# pc-001.net
KiCad netlist of a schematic drawn in EAGLE
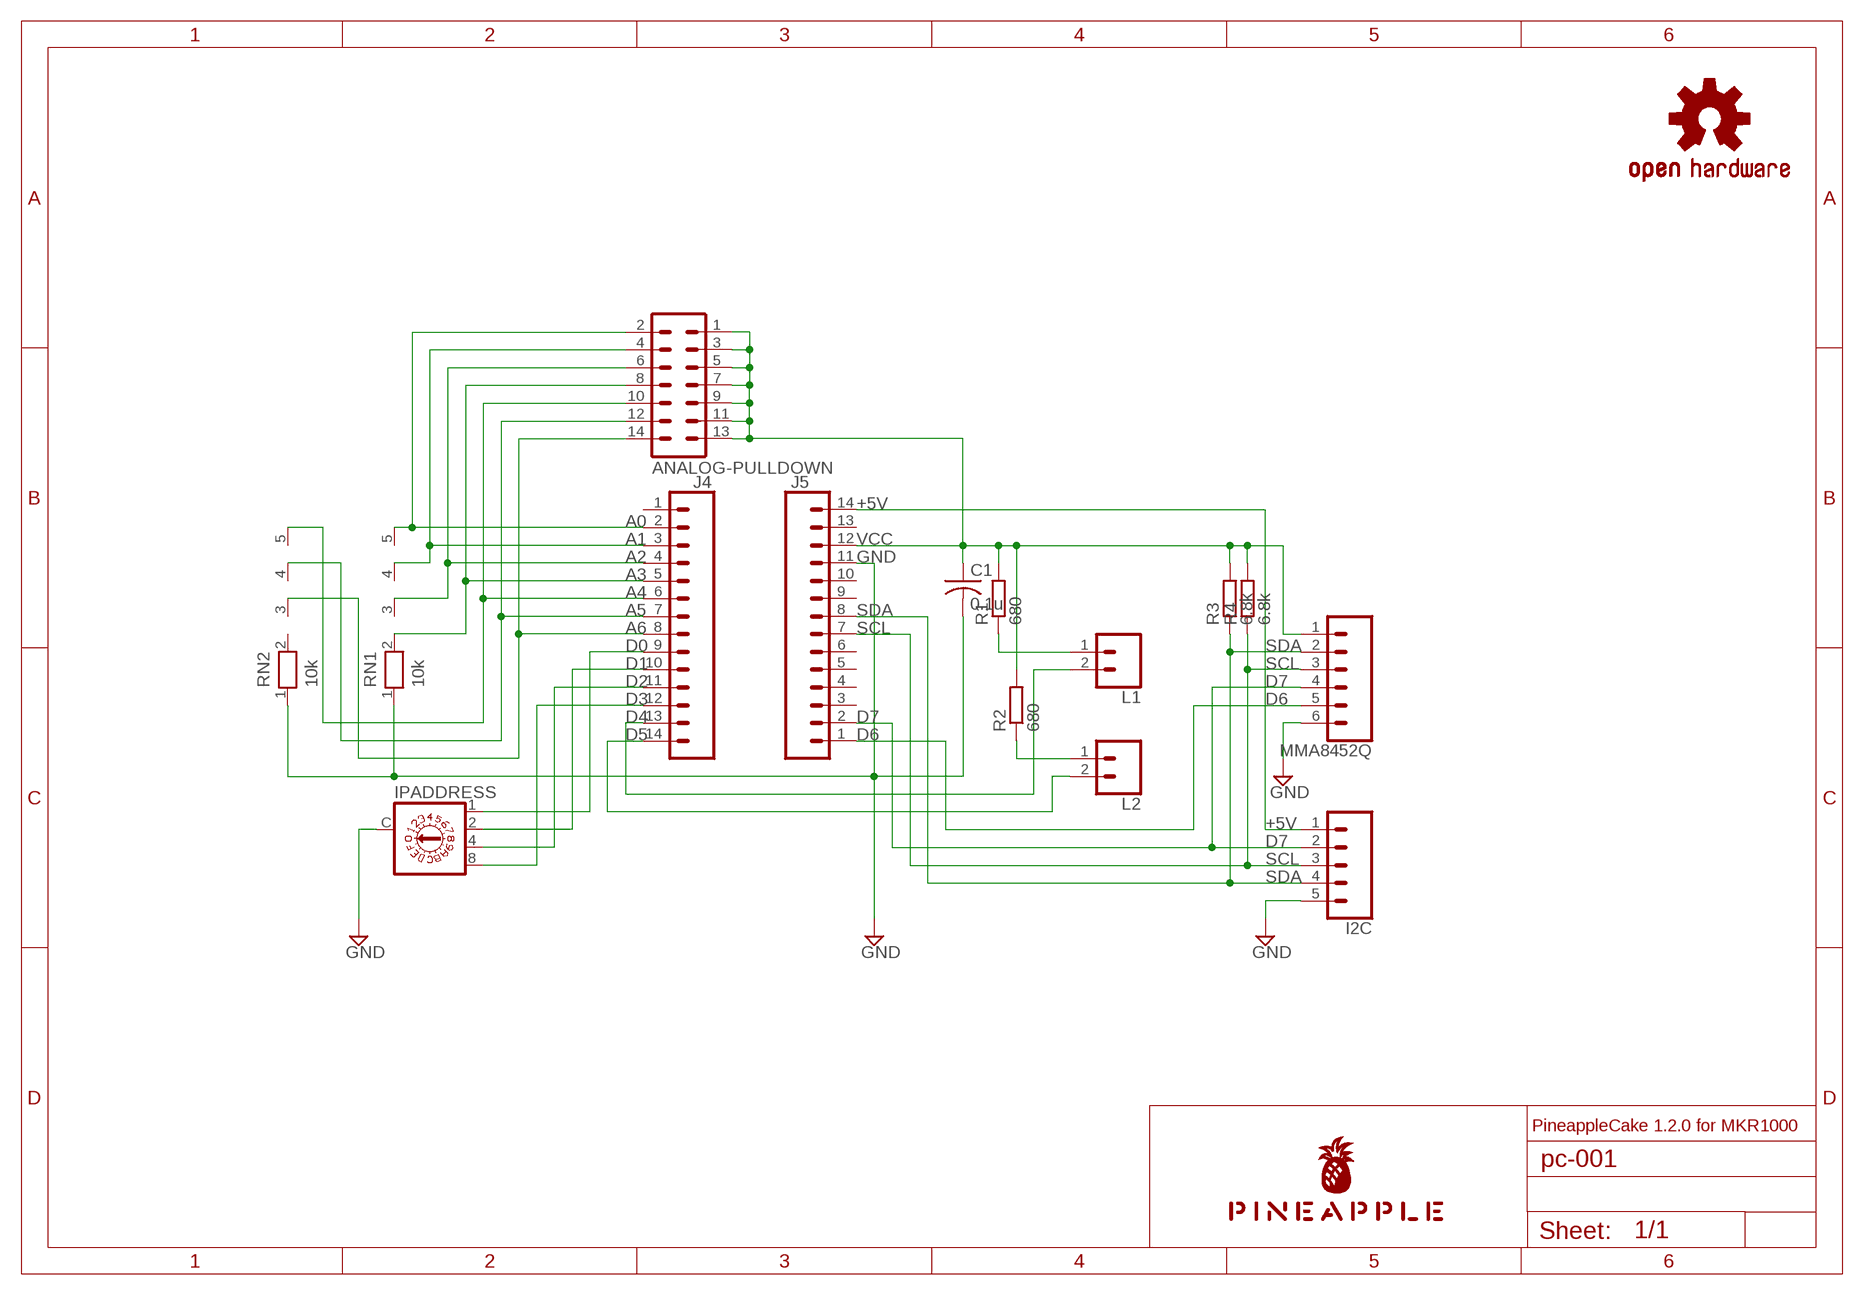
[diagram p0: schematic, sheet 1]

(export (version "E")
  (design (tool "Eeschema 10.0.6"))
  (components
    (comp (ref "ANALOG-PULLDOWN")
      (value "ML14L")
      (footprint "eagle-import:ML14L")
      (libsource (lib "eagle-import") (part "ML14L"))
    )
    (comp (ref "C1")
      (value "0.1u")
      (footprint "eagle-import:C025-025X050")
      (libsource (lib "eagle-import") (part "C-US025-025X050"))
    )
    (comp (ref "I2C")
      (value "CONN_05SMD")
      (footprint "eagle-import:1X05_1MM")
      (libsource (lib "eagle-import") (part "CONN_05SMD"))
    )
    (comp (ref "IPADDRESS")
      (value "A1353HEX")
      (footprint "eagle-import:A1353HEX")
      (libsource (lib "eagle-import") (part "A1353HEX"))
    )
    (comp (ref "J4")
      (value "DNP")
      (footprint "eagle-import:1X14")
      (libsource (lib "eagle-import") (part "CONN_14"))
    )
    (comp (ref "J5")
      (value "DNP")
      (footprint "eagle-import:1X14")
      (libsource (lib "eagle-import") (part "CONN_14"))
    )
    (comp (ref "L1")
      (value "CONN_02-JST-2-PTH-NO_SILK")
      (footprint "eagle-import:JST-2-PTH-NS")
      (libsource (lib "eagle-import") (part "CONN_02-JST-2-PTH-NO_SILK"))
    )
    (comp (ref "L2")
      (value "CONN_02-JST-2-PTH-NO_SILK")
      (footprint "eagle-import:JST-2-PTH-NS")
      (libsource (lib "eagle-import") (part "CONN_02-JST-2-PTH-NO_SILK"))
    )
    (comp (ref "LOGO1")
      (value "OSHW-LOGOS-COPPER")
      (footprint "eagle-import:OSHW-LOGO-S_COPPER")
      (libsource (lib "eagle-import") (part "OSHW-LOGOS-COPPER"))
    )
    (comp (ref "MMA8452Q")
      (value "CONN_06NO_SILK_FEMALE_PTH")
      (footprint "eagle-import:1X06_NO_SILK")
      (libsource (lib "eagle-import") (part "CONN_06NO_SILK_FEMALE_PTH"))
    )
    (comp (ref "R1")
      (value "680")
      (footprint "eagle-import:0204_5")
      (libsource (lib "eagle-import") (part "R-EU_0204/5"))
    )
    (comp (ref "R2")
      (value "680")
      (footprint "eagle-import:0204_5")
      (libsource (lib "eagle-import") (part "R-EU_0204/5"))
    )
    (comp (ref "R3")
      (value "6.8k")
      (footprint "eagle-import:0204_5")
      (libsource (lib "eagle-import") (part "R-EU_0204/5"))
    )
    (comp (ref "R4")
      (value "6.8k")
      (footprint "eagle-import:0204_5")
      (libsource (lib "eagle-import") (part "R-EU_0204/5"))
    )
    (comp (ref "RN1")
      (value "10k")
      (footprint "eagle-import:RN-5")
      (libsource (lib "eagle-import") (part "RN04"))
    )
    (comp (ref "RN2")
      (value "10k")
      (footprint "eagle-import:RN-5")
      (libsource (lib "eagle-import") (part "RN04"))
    )
    (comp (ref "U$1")
      (value "PINEAPPLE450")
      (footprint "eagle-import:PINEAPPLE450")
      (libsource (lib "eagle-import") (part "PINEAPPLE450"))
    )
  )
  (nets
    (net (code "1") (name "/+5V") (class "Default")
      (node (ref "I2C") (pin "1") (pinfunction "1_1") (pintype "passive"))
      (node (ref "J5") (pin "14") (pinfunction "14_14") (pintype "passive"))
    )
    (net (code "2") (name "/A0") (class "Default")
      (node (ref "ANALOG-PULLDOWN") (pin "2") (pinfunction "2_2") (pintype "passive"))
      (node (ref "J4") (pin "2") (pinfunction "2_2") (pintype "passive"))
      (node (ref "RN1") (pin "5") (pinfunction "5_5") (pintype "passive"))
    )
    (net (code "3") (name "/A1") (class "Default")
      (node (ref "ANALOG-PULLDOWN") (pin "4") (pinfunction "4_4") (pintype "passive"))
      (node (ref "J4") (pin "3") (pinfunction "3_3") (pintype "passive"))
      (node (ref "RN1") (pin "4") (pinfunction "4_4") (pintype "passive"))
    )
    (net (code "4") (name "/A2") (class "Default")
      (node (ref "ANALOG-PULLDOWN") (pin "6") (pinfunction "6_6") (pintype "passive"))
      (node (ref "J4") (pin "4") (pinfunction "4_4") (pintype "passive"))
      (node (ref "RN1") (pin "3") (pinfunction "3_3") (pintype "passive"))
    )
    (net (code "5") (name "/A3") (class "Default")
      (node (ref "ANALOG-PULLDOWN") (pin "8") (pinfunction "8_8") (pintype "passive"))
      (node (ref "J4") (pin "5") (pinfunction "5_5") (pintype "passive"))
      (node (ref "RN1") (pin "2") (pinfunction "2_2") (pintype "passive"))
    )
    (net (code "6") (name "/A4") (class "Default")
      (node (ref "ANALOG-PULLDOWN") (pin "10") (pinfunction "10_10") (pintype "passive"))
      (node (ref "J4") (pin "6") (pinfunction "6_6") (pintype "passive"))
      (node (ref "RN2") (pin "5") (pinfunction "5_5") (pintype "passive"))
    )
    (net (code "7") (name "/A5") (class "Default")
      (node (ref "ANALOG-PULLDOWN") (pin "12") (pinfunction "12_12") (pintype "passive"))
      (node (ref "J4") (pin "7") (pinfunction "7_7") (pintype "passive"))
      (node (ref "RN2") (pin "4") (pinfunction "4_4") (pintype "passive"))
    )
    (net (code "8") (name "/A6") (class "Default")
      (node (ref "ANALOG-PULLDOWN") (pin "14") (pinfunction "14_14") (pintype "passive"))
      (node (ref "J4") (pin "8") (pinfunction "8_8") (pintype "passive"))
      (node (ref "RN2") (pin "3") (pinfunction "3_3") (pintype "passive"))
    )
    (net (code "9") (name "/D0") (class "Default")
      (node (ref "IPADDRESS") (pin "1") (pinfunction "1_1") (pintype "passive"))
      (node (ref "J4") (pin "9") (pinfunction "9_9") (pintype "passive"))
    )
    (net (code "10") (name "/D1") (class "Default")
      (node (ref "IPADDRESS") (pin "2") (pinfunction "2_2") (pintype "passive"))
      (node (ref "J4") (pin "10") (pinfunction "10_10") (pintype "passive"))
    )
    (net (code "11") (name "/D2") (class "Default")
      (node (ref "IPADDRESS") (pin "4") (pinfunction "4_4") (pintype "passive"))
      (node (ref "J4") (pin "11") (pinfunction "11_11") (pintype "passive"))
    )
    (net (code "12") (name "/D3") (class "Default")
      (node (ref "IPADDRESS") (pin "8") (pinfunction "8_8") (pintype "passive"))
      (node (ref "J4") (pin "12") (pinfunction "12_12") (pintype "passive"))
    )
    (net (code "13") (name "/D4") (class "Default")
      (node (ref "J4") (pin "13") (pinfunction "13_13") (pintype "passive"))
      (node (ref "L1") (pin "2") (pinfunction "2_2") (pintype "passive"))
    )
    (net (code "14") (name "/D5") (class "Default")
      (node (ref "J4") (pin "14") (pinfunction "14_14") (pintype "passive"))
      (node (ref "L2") (pin "2") (pinfunction "2_2") (pintype "passive"))
    )
    (net (code "15") (name "/D6") (class "Default")
      (node (ref "J5") (pin "1") (pinfunction "1_1") (pintype "passive"))
      (node (ref "MMA8452Q") (pin "5") (pinfunction "5_5") (pintype "passive"))
    )
    (net (code "16") (name "/D7") (class "Default")
      (node (ref "I2C") (pin "2") (pinfunction "2_2") (pintype "passive"))
      (node (ref "J5") (pin "2") (pinfunction "2_2") (pintype "passive"))
      (node (ref "MMA8452Q") (pin "4") (pinfunction "4_4") (pintype "passive"))
    )
    (net (code "17") (name "/SCL") (class "Default")
      (node (ref "I2C") (pin "3") (pinfunction "3_3") (pintype "passive"))
      (node (ref "J5") (pin "7") (pinfunction "7_7") (pintype "passive"))
      (node (ref "MMA8452Q") (pin "3") (pinfunction "3_3") (pintype "passive"))
      (node (ref "R4") (pin "1") (pinfunction "1_1") (pintype "passive"))
    )
    (net (code "18") (name "/SDA") (class "Default")
      (node (ref "I2C") (pin "4") (pinfunction "4_4") (pintype "passive"))
      (node (ref "J5") (pin "8") (pinfunction "8_8") (pintype "passive"))
      (node (ref "MMA8452Q") (pin "2") (pinfunction "2_2") (pintype "passive"))
      (node (ref "R3") (pin "1") (pinfunction "1_1") (pintype "passive"))
    )
    (net (code "19") (name "/VCC") (class "Default")
      (node (ref "ANALOG-PULLDOWN") (pin "1") (pinfunction "1_1") (pintype "passive"))
      (node (ref "ANALOG-PULLDOWN") (pin "11") (pinfunction "11_11") (pintype "passive"))
      (node (ref "ANALOG-PULLDOWN") (pin "13") (pinfunction "13_13") (pintype "passive"))
      (node (ref "ANALOG-PULLDOWN") (pin "3") (pinfunction "3_3") (pintype "passive"))
      (node (ref "ANALOG-PULLDOWN") (pin "5") (pinfunction "5_5") (pintype "passive"))
      (node (ref "ANALOG-PULLDOWN") (pin "7") (pinfunction "7_7") (pintype "passive"))
      (node (ref "ANALOG-PULLDOWN") (pin "9") (pinfunction "9_9") (pintype "passive"))
      (node (ref "C1") (pin "1") (pinfunction "1_1") (pintype "passive"))
      (node (ref "J5") (pin "12") (pinfunction "12_12") (pintype "passive"))
      (node (ref "MMA8452Q") (pin "1") (pinfunction "1_1") (pintype "passive"))
      (node (ref "R1") (pin "2") (pinfunction "2_2") (pintype "passive"))
      (node (ref "R2") (pin "2") (pinfunction "2_2") (pintype "passive"))
      (node (ref "R3") (pin "2") (pinfunction "2_2") (pintype "passive"))
      (node (ref "R4") (pin "2") (pinfunction "2_2") (pintype "passive"))
    )
    (net (code "20") (name "GND") (class "Default")
      (node (ref "C1") (pin "2") (pinfunction "2_2") (pintype "passive"))
      (node (ref "I2C") (pin "5") (pinfunction "5_5") (pintype "passive"))
      (node (ref "IPADDRESS") (pin "C") (pinfunction "C_C") (pintype "passive"))
      (node (ref "J5") (pin "11") (pinfunction "11_11") (pintype "passive"))
      (node (ref "MMA8452Q") (pin "6") (pinfunction "6_6") (pintype "passive"))
      (node (ref "RN1") (pin "1") (pinfunction "1_1") (pintype "passive"))
      (node (ref "RN2") (pin "1") (pinfunction "1_1") (pintype "passive"))
    )
    (net (code "21") (name "Net-(L1-Pad1)") (class "Default")
      (node (ref "L1") (pin "1") (pinfunction "1_1") (pintype "passive"))
      (node (ref "R1") (pin "1") (pinfunction "1_1") (pintype "passive"))
    )
    (net (code "22") (name "Net-(L2-Pad1)") (class "Default")
      (node (ref "L2") (pin "1") (pinfunction "1_1") (pintype "passive"))
      (node (ref "R2") (pin "1") (pinfunction "1_1") (pintype "passive"))
    )
    (net (code "23") (name "unconnected-(J4-Pad1)") (class "Default")
      (node (ref "J4") (pin "1") (pinfunction "1_1") (pintype "passive"))
    )
    (net (code "24") (name "unconnected-(J5-Pad3)") (class "Default")
      (node (ref "J5") (pin "3") (pinfunction "3_3") (pintype "passive"))
    )
    (net (code "25") (name "unconnected-(J5-Pad4)") (class "Default")
      (node (ref "J5") (pin "4") (pinfunction "4_4") (pintype "passive"))
    )
    (net (code "26") (name "unconnected-(J5-Pad5)") (class "Default")
      (node (ref "J5") (pin "5") (pinfunction "5_5") (pintype "passive"))
    )
    (net (code "27") (name "unconnected-(J5-Pad6)") (class "Default")
      (node (ref "J5") (pin "6") (pinfunction "6_6") (pintype "passive"))
    )
    (net (code "28") (name "unconnected-(J5-Pad9)") (class "Default")
      (node (ref "J5") (pin "9") (pinfunction "9_9") (pintype "passive"))
    )
    (net (code "29") (name "unconnected-(J5-Pad10)") (class "Default")
      (node (ref "J5") (pin "10") (pinfunction "10_10") (pintype "passive"))
    )
    (net (code "30") (name "unconnected-(J5-Pad13)") (class "Default")
      (node (ref "J5") (pin "13") (pinfunction "13_13") (pintype "passive"))
    )
    (net (code "31") (name "unconnected-(RN2-Pad2)") (class "Default")
      (node (ref "RN2") (pin "2") (pinfunction "2_2") (pintype "passive"))
    )
  )
)
